# D.net
KiCad netlist of a schematic drawn in EAGLE
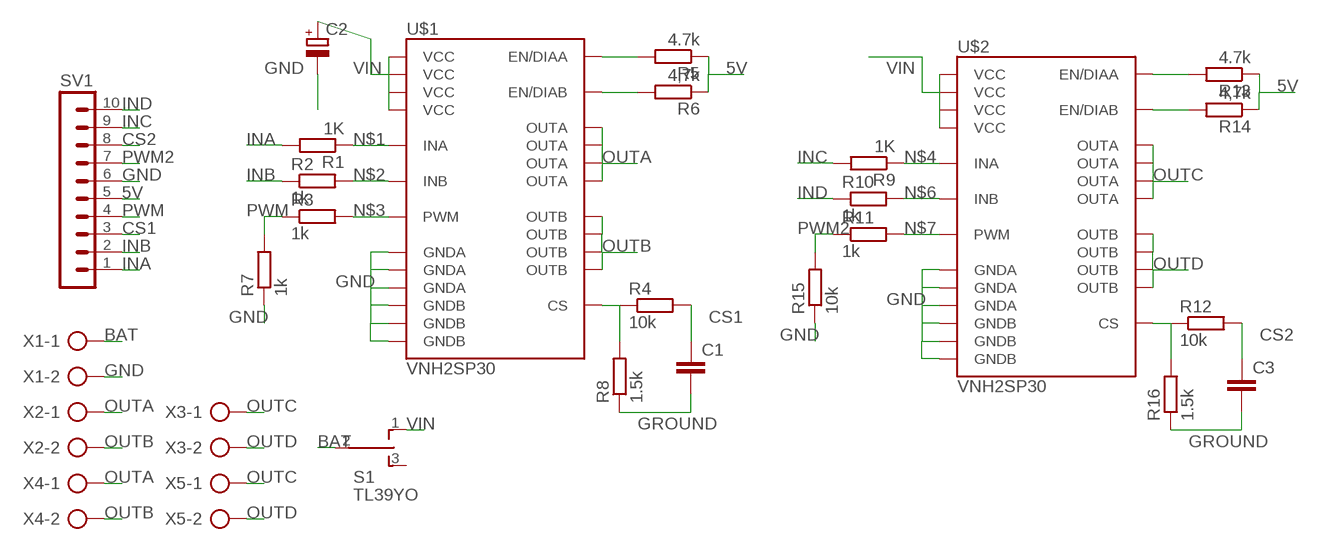
[diagram p0: schematic, sheet 1]

(export (version "E")
  (design (tool "Eeschema 10.0.6"))
  (components
    (comp (ref "C1")
      (value "CAP1206")
      (footprint "eagle-import:1206")
      (libsource (lib "eagle-import") (part "CAP1206"))
    )
    (comp (ref "C2")
      (value "CPOL-EUE3.5-8")
      (footprint "eagle-import:E3,5-8")
      (libsource (lib "eagle-import") (part "CPOL-EUE3.5-8"))
    )
    (comp (ref "C3")
      (value "CAP1206")
      (footprint "eagle-import:1206")
      (libsource (lib "eagle-import") (part "CAP1206"))
    )
    (comp (ref "R1")
      (value "1K")
      (footprint "eagle-import:M1206")
      (libsource (lib "eagle-import") (part "R-EU_M1206"))
    )
    (comp (ref "R2")
      (value "1k")
      (footprint "eagle-import:M1206")
      (libsource (lib "eagle-import") (part "R-EU_M1206"))
    )
    (comp (ref "R3")
      (value "1k")
      (footprint "eagle-import:M1206")
      (libsource (lib "eagle-import") (part "R-EU_M1206"))
    )
    (comp (ref "R4")
      (value "10k")
      (footprint "eagle-import:M1206")
      (libsource (lib "eagle-import") (part "R-EU_M1206"))
    )
    (comp (ref "R5")
      (value "4.7k")
      (footprint "eagle-import:M1206")
      (libsource (lib "eagle-import") (part "R-EU_M1206"))
    )
    (comp (ref "R6")
      (value "4,7k")
      (footprint "eagle-import:M1206")
      (libsource (lib "eagle-import") (part "R-EU_M1206"))
    )
    (comp (ref "R7")
      (value "1k")
      (footprint "eagle-import:M1206")
      (libsource (lib "eagle-import") (part "R-EU_M1206"))
    )
    (comp (ref "R8")
      (value "1.5k")
      (footprint "eagle-import:M1206")
      (libsource (lib "eagle-import") (part "R-EU_M1206"))
    )
    (comp (ref "R9")
      (value "1K")
      (footprint "eagle-import:M1206")
      (libsource (lib "eagle-import") (part "R-EU_M1206"))
    )
    (comp (ref "R10")
      (value "1k")
      (footprint "eagle-import:M1206")
      (libsource (lib "eagle-import") (part "R-EU_M1206"))
    )
    (comp (ref "R11")
      (value "1k")
      (footprint "eagle-import:M1206")
      (libsource (lib "eagle-import") (part "R-EU_M1206"))
    )
    (comp (ref "R12")
      (value "10k")
      (footprint "eagle-import:M1206")
      (libsource (lib "eagle-import") (part "R-EU_M1206"))
    )
    (comp (ref "R13")
      (value "4.7k")
      (footprint "eagle-import:M1206")
      (libsource (lib "eagle-import") (part "R-EU_M1206"))
    )
    (comp (ref "R14")
      (value "4,7k")
      (footprint "eagle-import:M1206")
      (libsource (lib "eagle-import") (part "R-EU_M1206"))
    )
    (comp (ref "R15")
      (value "10k")
      (footprint "eagle-import:M1206")
      (libsource (lib "eagle-import") (part "R-EU_M1206"))
    )
    (comp (ref "R16")
      (value "1.5k")
      (footprint "eagle-import:M1206")
      (libsource (lib "eagle-import") (part "R-EU_M1206"))
    )
    (comp (ref "S1")
      (value "TL39YO")
      (footprint "eagle-import:TL3XYO")
      (libsource (lib "eagle-import") (part "TL39YO"))
    )
    (comp (ref "SV1")
      (value "MA10-1W")
      (footprint "eagle-import:MA10-1W")
      (libsource (lib "eagle-import") (part "MA10-1W"))
    )
    (comp (ref "U$1")
      (value "VNH2SP30")
      (footprint "eagle-import:VNH2SP30")
      (libsource (lib "eagle-import") (part "VNH2SP30"))
    )
    (comp (ref "U$2")
      (value "VNH2SP30")
      (footprint "eagle-import:VNH2SP30")
      (libsource (lib "eagle-import") (part "VNH2SP30"))
    )
    (comp (ref "X1")
      (value "AK300/2")
      (footprint "eagle-import:AK300_2")
      (libsource (lib "eagle-import") (part "AK300/2"))
    )
    (comp (ref "X2")
      (value "AK300/2")
      (footprint "eagle-import:AK300_2")
      (libsource (lib "eagle-import") (part "AK300/2"))
    )
    (comp (ref "X3")
      (value "AK300/2")
      (footprint "eagle-import:AK300_2")
      (libsource (lib "eagle-import") (part "AK300/2"))
    )
    (comp (ref "X4")
      (value "AK300/2")
      (footprint "eagle-import:AK300_2")
      (libsource (lib "eagle-import") (part "AK300/2"))
    )
    (comp (ref "X5")
      (value "AK300/2")
      (footprint "eagle-import:AK300_2")
      (libsource (lib "eagle-import") (part "AK300/2"))
    )
  )
  (nets
    (net (code "1") (name "/5V") (class "Default")
      (node (ref "R13") (pin "1") (pinfunction "1_1") (pintype "passive"))
      (node (ref "R14") (pin "1") (pinfunction "1_1") (pintype "passive"))
      (node (ref "R5") (pin "1") (pinfunction "1_1") (pintype "passive"))
      (node (ref "R6") (pin "1") (pinfunction "1_1") (pintype "passive"))
      (node (ref "SV1") (pin "5") (pinfunction "5_5") (pintype "passive"))
    )
    (net (code "2") (name "/BAT") (class "Default")
      (node (ref "S1") (pin "2") (pinfunction "P_2") (pintype "passive"))
      (node (ref "X1") (pin "1") (pinfunction "KL_1") (pintype "passive"))
    )
    (net (code "3") (name "/CS1") (class "Default")
      (node (ref "C1") (pin "1") (pinfunction "1_1") (pintype "passive"))
      (node (ref "R4") (pin "2") (pinfunction "2_2") (pintype "passive"))
      (node (ref "SV1") (pin "3") (pinfunction "3_3") (pintype "passive"))
    )
    (net (code "4") (name "/CS2") (class "Default")
      (node (ref "C3") (pin "1") (pinfunction "1_1") (pintype "passive"))
      (node (ref "R12") (pin "2") (pinfunction "2_2") (pintype "passive"))
      (node (ref "SV1") (pin "8") (pinfunction "8_8") (pintype "passive"))
    )
    (net (code "5") (name "/GND") (class "Default")
      (node (ref "C2") (pin "-") (pinfunction "-_-") (pintype "passive"))
      (node (ref "R15") (pin "1") (pinfunction "1_1") (pintype "passive"))
      (node (ref "R7") (pin "1") (pinfunction "1_1") (pintype "passive"))
      (node (ref "SV1") (pin "6") (pinfunction "6_6") (pintype "passive"))
      (node (ref "U$1") (pin "18") (pinfunction "GNDB_18") (pintype "bidirectional"))
      (node (ref "U$1") (pin "19") (pinfunction "GNDB_19") (pintype "bidirectional"))
      (node (ref "U$1") (pin "20") (pinfunction "GNDB_20") (pintype "bidirectional"))
      (node (ref "U$1") (pin "26") (pinfunction "GNDA_26") (pintype "bidirectional"))
      (node (ref "U$1") (pin "27") (pinfunction "GNDA_27") (pintype "bidirectional"))
      (node (ref "U$1") (pin "28") (pinfunction "GNDA_28") (pintype "bidirectional"))
      (node (ref "U$2") (pin "18") (pinfunction "GNDB_18") (pintype "bidirectional"))
      (node (ref "U$2") (pin "19") (pinfunction "GNDB_19") (pintype "bidirectional"))
      (node (ref "U$2") (pin "20") (pinfunction "GNDB_20") (pintype "bidirectional"))
      (node (ref "U$2") (pin "26") (pinfunction "GNDA_26") (pintype "bidirectional"))
      (node (ref "U$2") (pin "27") (pinfunction "GNDA_27") (pintype "bidirectional"))
      (node (ref "U$2") (pin "28") (pinfunction "GNDA_28") (pintype "bidirectional"))
      (node (ref "X1") (pin "2") (pinfunction "KL_2") (pintype "passive"))
    )
    (net (code "6") (name "/GROUND") (class "Default")
      (node (ref "C1") (pin "2") (pinfunction "2_2") (pintype "passive"))
      (node (ref "C3") (pin "2") (pinfunction "2_2") (pintype "passive"))
      (node (ref "R16") (pin "1") (pinfunction "1_1") (pintype "passive"))
      (node (ref "R8") (pin "1") (pinfunction "1_1") (pintype "passive"))
    )
    (net (code "7") (name "/INA") (class "Default")
      (node (ref "R1") (pin "2") (pinfunction "2_2") (pintype "passive"))
      (node (ref "SV1") (pin "1") (pinfunction "1_1") (pintype "passive"))
    )
    (net (code "8") (name "/INB") (class "Default")
      (node (ref "R2") (pin "1") (pinfunction "1_1") (pintype "passive"))
      (node (ref "SV1") (pin "2") (pinfunction "2_2") (pintype "passive"))
    )
    (net (code "9") (name "/INC") (class "Default")
      (node (ref "R9") (pin "2") (pinfunction "2_2") (pintype "passive"))
      (node (ref "SV1") (pin "9") (pinfunction "9_9") (pintype "passive"))
    )
    (net (code "10") (name "/IND") (class "Default")
      (node (ref "R10") (pin "1") (pinfunction "1_1") (pintype "passive"))
      (node (ref "SV1") (pin "10") (pinfunction "10_10") (pintype "passive"))
    )
    (net (code "11") (name "/N$1") (class "Default")
      (node (ref "R1") (pin "1") (pinfunction "1_1") (pintype "passive"))
      (node (ref "U$1") (pin "5") (pinfunction "INA_5") (pintype "bidirectional"))
    )
    (net (code "12") (name "/N$2") (class "Default")
      (node (ref "R2") (pin "2") (pinfunction "2_2") (pintype "passive"))
      (node (ref "U$1") (pin "11") (pinfunction "INB_11") (pintype "bidirectional"))
    )
    (net (code "13") (name "/N$3") (class "Default")
      (node (ref "R3") (pin "2") (pinfunction "2_2") (pintype "passive"))
      (node (ref "U$1") (pin "8") (pinfunction "PWM_8") (pintype "bidirectional"))
    )
    (net (code "14") (name "/N$4") (class "Default")
      (node (ref "R9") (pin "1") (pinfunction "1_1") (pintype "passive"))
      (node (ref "U$2") (pin "5") (pinfunction "INA_5") (pintype "bidirectional"))
    )
    (net (code "15") (name "/N$6") (class "Default")
      (node (ref "R10") (pin "2") (pinfunction "2_2") (pintype "passive"))
      (node (ref "U$2") (pin "11") (pinfunction "INB_11") (pintype "bidirectional"))
    )
    (net (code "16") (name "/N$7") (class "Default")
      (node (ref "R11") (pin "2") (pinfunction "2_2") (pintype "passive"))
      (node (ref "U$2") (pin "8") (pinfunction "PWM_8") (pintype "bidirectional"))
    )
    (net (code "17") (name "/OUTA") (class "Default")
      (node (ref "U$1") (pin "1") (pinfunction "OUTA_1") (pintype "bidirectional"))
      (node (ref "U$1") (pin "25") (pinfunction "OUTA_25") (pintype "bidirectional"))
      (node (ref "U$1") (pin "30") (pinfunction "OUTA_30") (pintype "bidirectional"))
      (node (ref "U$1") (pin "SLUG3") (pinfunction "OUTA_SLUG3") (pintype "bidirectional"))
      (node (ref "X2") (pin "1") (pinfunction "KL_1") (pintype "passive"))
      (node (ref "X4") (pin "1") (pinfunction "KL_1") (pintype "passive"))
    )
    (net (code "18") (name "/OUTB") (class "Default")
      (node (ref "U$1") (pin "15") (pinfunction "OUTB_15") (pintype "bidirectional"))
      (node (ref "U$1") (pin "16") (pinfunction "OUTB_16") (pintype "bidirectional"))
      (node (ref "U$1") (pin "21") (pinfunction "OUTB_21") (pintype "bidirectional"))
      (node (ref "U$1") (pin "SLUG2") (pinfunction "OUTB_SLUG2") (pintype "bidirectional"))
      (node (ref "X2") (pin "2") (pinfunction "KL_2") (pintype "passive"))
      (node (ref "X4") (pin "2") (pinfunction "KL_2") (pintype "passive"))
    )
    (net (code "19") (name "/OUTC") (class "Default")
      (node (ref "U$2") (pin "1") (pinfunction "OUTA_1") (pintype "bidirectional"))
      (node (ref "U$2") (pin "25") (pinfunction "OUTA_25") (pintype "bidirectional"))
      (node (ref "U$2") (pin "30") (pinfunction "OUTA_30") (pintype "bidirectional"))
      (node (ref "U$2") (pin "SLUG3") (pinfunction "OUTA_SLUG3") (pintype "bidirectional"))
      (node (ref "X3") (pin "1") (pinfunction "KL_1") (pintype "passive"))
      (node (ref "X5") (pin "1") (pinfunction "KL_1") (pintype "passive"))
    )
    (net (code "20") (name "/OUTD") (class "Default")
      (node (ref "U$2") (pin "15") (pinfunction "OUTB_15") (pintype "bidirectional"))
      (node (ref "U$2") (pin "16") (pinfunction "OUTB_16") (pintype "bidirectional"))
      (node (ref "U$2") (pin "21") (pinfunction "OUTB_21") (pintype "bidirectional"))
      (node (ref "U$2") (pin "SLUG2") (pinfunction "OUTB_SLUG2") (pintype "bidirectional"))
      (node (ref "X3") (pin "2") (pinfunction "KL_2") (pintype "passive"))
      (node (ref "X5") (pin "2") (pinfunction "KL_2") (pintype "passive"))
    )
    (net (code "21") (name "/PWM") (class "Default")
      (node (ref "R3") (pin "1") (pinfunction "1_1") (pintype "passive"))
      (node (ref "R7") (pin "2") (pinfunction "2_2") (pintype "passive"))
      (node (ref "SV1") (pin "4") (pinfunction "4_4") (pintype "passive"))
    )
    (net (code "22") (name "/PWM2") (class "Default")
      (node (ref "R11") (pin "1") (pinfunction "1_1") (pintype "passive"))
      (node (ref "R15") (pin "2") (pinfunction "2_2") (pintype "passive"))
      (node (ref "SV1") (pin "7") (pinfunction "7_7") (pintype "passive"))
    )
    (net (code "23") (name "/VIN") (class "Default")
      (node (ref "C2") (pin "+") (pinfunction "+_+") (pintype "passive"))
      (node (ref "S1") (pin "1") (pinfunction "O_1") (pintype "passive"))
      (node (ref "U$1") (pin "13") (pinfunction "VCC_13") (pintype "bidirectional"))
      (node (ref "U$1") (pin "23") (pinfunction "VCC_23") (pintype "bidirectional"))
      (node (ref "U$1") (pin "3") (pinfunction "VCC_3") (pintype "bidirectional"))
      (node (ref "U$1") (pin "SLUG1") (pinfunction "VCC_SLUG1") (pintype "bidirectional"))
      (node (ref "U$2") (pin "13") (pinfunction "VCC_13") (pintype "bidirectional"))
      (node (ref "U$2") (pin "23") (pinfunction "VCC_23") (pintype "bidirectional"))
      (node (ref "U$2") (pin "3") (pinfunction "VCC_3") (pintype "bidirectional"))
      (node (ref "U$2") (pin "SLUG1") (pinfunction "VCC_SLUG1") (pintype "bidirectional"))
    )
    (net (code "24") (name "Net-(U$1-CS)") (class "Default")
      (node (ref "R4") (pin "1") (pinfunction "1_1") (pintype "passive"))
      (node (ref "R8") (pin "2") (pinfunction "2_2") (pintype "passive"))
      (node (ref "U$1") (pin "9") (pinfunction "CS_9") (pintype "bidirectional"))
    )
    (net (code "25") (name "Net-(U$1-EN{slash}DIAA)") (class "Default")
      (node (ref "R5") (pin "2") (pinfunction "2_2") (pintype "passive"))
      (node (ref "U$1") (pin "6") (pinfunction "EN/DIAA_6") (pintype "bidirectional"))
    )
    (net (code "26") (name "Net-(U$1-EN{slash}DIAB)") (class "Default")
      (node (ref "R6") (pin "2") (pinfunction "2_2") (pintype "passive"))
      (node (ref "U$1") (pin "10") (pinfunction "EN/DIAB_10") (pintype "bidirectional"))
    )
    (net (code "27") (name "Net-(U$2-CS)") (class "Default")
      (node (ref "R12") (pin "1") (pinfunction "1_1") (pintype "passive"))
      (node (ref "R16") (pin "2") (pinfunction "2_2") (pintype "passive"))
      (node (ref "U$2") (pin "9") (pinfunction "CS_9") (pintype "bidirectional"))
    )
    (net (code "28") (name "Net-(U$2-EN{slash}DIAA)") (class "Default")
      (node (ref "R13") (pin "2") (pinfunction "2_2") (pintype "passive"))
      (node (ref "U$2") (pin "6") (pinfunction "EN/DIAA_6") (pintype "bidirectional"))
    )
    (net (code "29") (name "Net-(U$2-EN{slash}DIAB)") (class "Default")
      (node (ref "R14") (pin "2") (pinfunction "2_2") (pintype "passive"))
      (node (ref "U$2") (pin "10") (pinfunction "EN/DIAB_10") (pintype "bidirectional"))
    )
    (net (code "30") (name "unconnected-(S1-S-Pad3)") (class "Default")
      (node (ref "S1") (pin "3") (pinfunction "S_3") (pintype "passive"))
    )
  )
)
